# modulo_LCD_ShiftRegister_SCH.net
KiCad netlist of a schematic drawn in Altium Designer
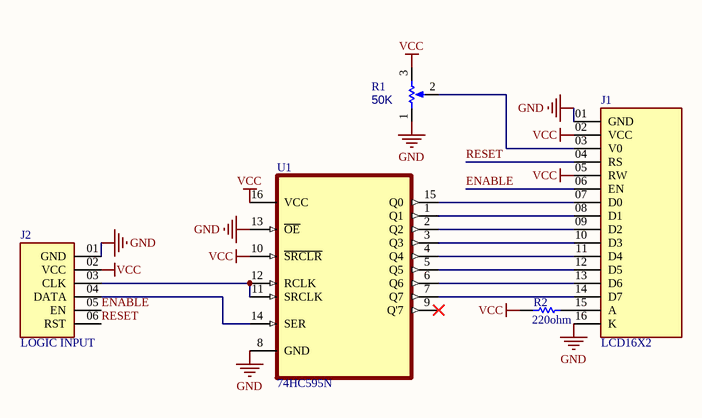
[diagram p0: modulo_LCD_ShiftRegister_SCH.SchDoc]

(export (version "E")
  (design (tool "Eeschema 10.0.6"))
  (components
    (comp (ref "J1")
      (value "LCD16X2")
      (footprint "HEADER 16 PIN")
      (fields (field (name "MP") "TSW-116-07-T-S-LL"))
      (libsource (lib "Schlib1") (part "LCD16X2"))
    )
    (comp (ref "J2")
      (value "LOGIC INPUT")
      (footprint "HEADER 6 PIN")
      (description "Connector Header Through Hole 6 position 0.100 (2.54mm)")
      (fields (field (name "MF") "Samtec") (field (name "MP") "TSW-106-26-T-S"))
      (libsource (lib "Schlib1") (part "LOGIC INPUT"))
    )
    (comp (ref "R1")
      (value "50K")
      (footprint "TRIMMING POTENTIOMETER")
      (description "4K7")
      (libsource (lib "Schlib1") (part "Potentiometer"))
    )
    (comp (ref "R2")
      (value "220ohm")
      (footprint "Res Axial 0.5")
      (description "Resistor")
      (fields (field (name "PUBLISHER") "Altium Limited"))
      (libsource (lib "Schlib1") (part "Res1"))
    )
    (comp (ref "U1")
      (value "74HC595N")
      (footprint "DIP254P762X420-16")
      (description "Shift Shift Register 1 Element 8 Bit 16-DIP")
      (fields (field (name "MF") "NXP USA") (field (name "MP") "74HC595N,112"))
      (libsource (lib "Schlib1") (part "74HC595N,112"))
    )
  )
  (nets
    (net (code "1") (name "/ENABLE") (class "Default")
      (node (ref "J1") (pin "06") (pinfunction "EN_06") (pintype "passive"))
      (node (ref "J2") (pin "05") (pinfunction "EN_05") (pintype "passive"))
    )
    (net (code "2") (name "/RESET") (class "Default")
      (node (ref "J1") (pin "04") (pinfunction "RS_04") (pintype "passive"))
      (node (ref "J2") (pin "06") (pinfunction "RST_06") (pintype "passive"))
    )
    (net (code "3") (name "GND") (class "Default")
      (node (ref "J1") (pin "01") (pinfunction "GND_01") (pintype "passive"))
      (node (ref "J1") (pin "16") (pinfunction "K_16") (pintype "passive"))
      (node (ref "J2") (pin "01") (pinfunction "GND_01") (pintype "passive"))
      (node (ref "R1") (pin "1") (pinfunction "TOP_1") (pintype "passive"))
      (node (ref "U1") (pin "13") (pinfunction "~{OE}_13") (pintype "input"))
      (node (ref "U1") (pin "8") (pinfunction "GND_8") (pintype "passive"))
    )
    (net (code "4") (name "Net-(J1-A)") (class "Default")
      (node (ref "J1") (pin "15") (pinfunction "A_15") (pintype "passive"))
      (node (ref "R2") (pin "2") (pinfunction "2_2") (pintype "passive"))
    )
    (net (code "5") (name "Net-(J1-D0)") (class "Default")
      (node (ref "J1") (pin "07") (pinfunction "D0_07") (pintype "passive"))
      (node (ref "U1") (pin "15") (pinfunction "Q0_15") (pintype "output"))
    )
    (net (code "6") (name "Net-(J1-D1)") (class "Default")
      (node (ref "J1") (pin "08") (pinfunction "D1_08") (pintype "passive"))
      (node (ref "U1") (pin "1") (pinfunction "Q1_1") (pintype "output"))
    )
    (net (code "7") (name "Net-(J1-D2)") (class "Default")
      (node (ref "J1") (pin "09") (pinfunction "D2_09") (pintype "passive"))
      (node (ref "U1") (pin "2") (pinfunction "Q2_2") (pintype "output"))
    )
    (net (code "8") (name "Net-(J1-D3)") (class "Default")
      (node (ref "J1") (pin "10") (pinfunction "D3_10") (pintype "passive"))
      (node (ref "U1") (pin "3") (pinfunction "Q3_3") (pintype "output"))
    )
    (net (code "9") (name "Net-(J1-D4)") (class "Default")
      (node (ref "J1") (pin "11") (pinfunction "D4_11") (pintype "passive"))
      (node (ref "U1") (pin "4") (pinfunction "Q4_4") (pintype "output"))
    )
    (net (code "10") (name "Net-(J1-D5)") (class "Default")
      (node (ref "J1") (pin "12") (pinfunction "D5_12") (pintype "passive"))
      (node (ref "U1") (pin "5") (pinfunction "Q5_5") (pintype "output"))
    )
    (net (code "11") (name "Net-(J1-D6)") (class "Default")
      (node (ref "J1") (pin "13") (pinfunction "D6_13") (pintype "passive"))
      (node (ref "U1") (pin "6") (pinfunction "Q6_6") (pintype "output"))
    )
    (net (code "12") (name "Net-(J1-D7)") (class "Default")
      (node (ref "J1") (pin "14") (pinfunction "D7_14") (pintype "passive"))
      (node (ref "U1") (pin "7") (pinfunction "Q7_7") (pintype "output"))
    )
    (net (code "13") (name "Net-(J1-V0)") (class "Default")
      (node (ref "J1") (pin "03") (pinfunction "V0_03") (pintype "passive"))
      (node (ref "R1") (pin "2") (pinfunction "TAP_2") (pintype "passive"))
    )
    (net (code "14") (name "Net-(J2-CLK)") (class "Default")
      (node (ref "J2") (pin "03") (pinfunction "CLK_03") (pintype "passive"))
      (node (ref "U1") (pin "11") (pinfunction "SRCLK_11") (pintype "input"))
      (node (ref "U1") (pin "12") (pinfunction "RCLK_12") (pintype "input"))
    )
    (net (code "15") (name "Net-(J2-DATA)") (class "Default")
      (node (ref "J2") (pin "04") (pinfunction "DATA_04") (pintype "passive"))
      (node (ref "U1") (pin "14") (pinfunction "SER_14") (pintype "input"))
    )
    (net (code "16") (name "VCC") (class "Default")
      (node (ref "J1") (pin "02") (pinfunction "VCC_02") (pintype "passive"))
      (node (ref "J1") (pin "05") (pinfunction "RW_05") (pintype "passive"))
      (node (ref "J2") (pin "02") (pinfunction "VCC_02") (pintype "passive"))
      (node (ref "R1") (pin "3") (pinfunction "BOT_3") (pintype "passive"))
      (node (ref "R2") (pin "1") (pinfunction "1_1") (pintype "passive"))
      (node (ref "U1") (pin "10") (pinfunction "~{SRCLR}_10") (pintype "input"))
      (node (ref "U1") (pin "16") (pinfunction "VCC_16") (pintype "power_in"))
    )
    (net (code "17") (name "unconnected-(U1-Q'7-Pad9)") (class "Default")
      (node (ref "U1") (pin "9") (pinfunction "Q'7_9") (pintype "output+no_connect"))
    )
  )
)
